# 14_-MAIN_CONNECTORS.net
KiCad netlist of a schematic drawn in Altium Designer
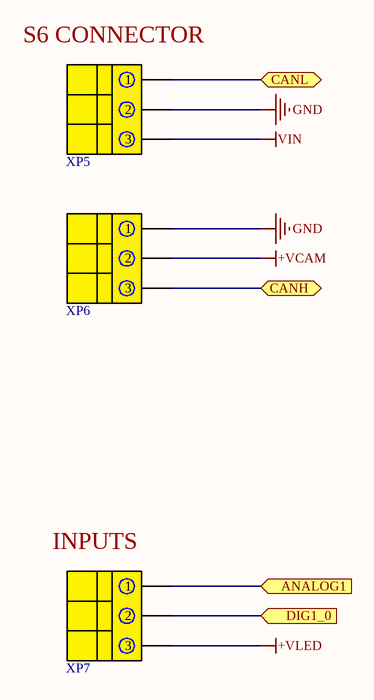
[diagram p0: [14]-MAIN_CONNECTORS.SchDoc]

(export (version "E")
  (design (tool "Eeschema 10.0.6"))
  (components
    (comp (ref "XP5")
      (value "DG330-3PIN")
      (footprint "DG330-3P")
      (description "Degson 3 pin connector rear")
      (libsource (lib "fizik_lib") (part "DG330-3P"))
    )
    (comp (ref "XP6")
      (value "DG330-3PIN")
      (footprint "DG330-3P")
      (description "Degson 3 pin connector rear")
      (libsource (lib "fizik_lib") (part "DG330-3P"))
    )
    (comp (ref "XP7")
      (value "DG330-3PIN")
      (footprint "DG330-3P")
      (description "Degson 3 pin connector rear")
      (libsource (lib "fizik_lib") (part "DG330-3P"))
    )
  )
  (nets
    (net (code "1") (name "+VCAM") (class "Default")
      (node (ref "XP6") (pin "2") (pinfunction "2_2") (pintype "passive"))
    )
    (net (code "2") (name "+VLED") (class "Default")
      (node (ref "XP7") (pin "3") (pinfunction "3_3") (pintype "passive"))
    )
    (net (code "3") (name "/ANALOG1") (class "Default")
      (node (ref "XP7") (pin "1") (pinfunction "1_1") (pintype "passive"))
    )
    (net (code "4") (name "/CANH") (class "Default")
      (node (ref "XP6") (pin "3") (pinfunction "3_3") (pintype "passive"))
    )
    (net (code "5") (name "/CANL") (class "Default")
      (node (ref "XP5") (pin "1") (pinfunction "1_1") (pintype "passive"))
    )
    (net (code "6") (name "/DIG1_0") (class "Default")
      (node (ref "XP7") (pin "2") (pinfunction "2_2") (pintype "passive"))
    )
    (net (code "7") (name "GND") (class "Default")
      (node (ref "XP5") (pin "2") (pinfunction "2_2") (pintype "passive"))
      (node (ref "XP6") (pin "1") (pinfunction "1_1") (pintype "passive"))
    )
    (net (code "8") (name "VIN") (class "Default")
      (node (ref "XP5") (pin "3") (pinfunction "3_3") (pintype "passive"))
    )
  )
)
